# Sheet1.net
KiCad netlist of a schematic drawn in Altium Designer
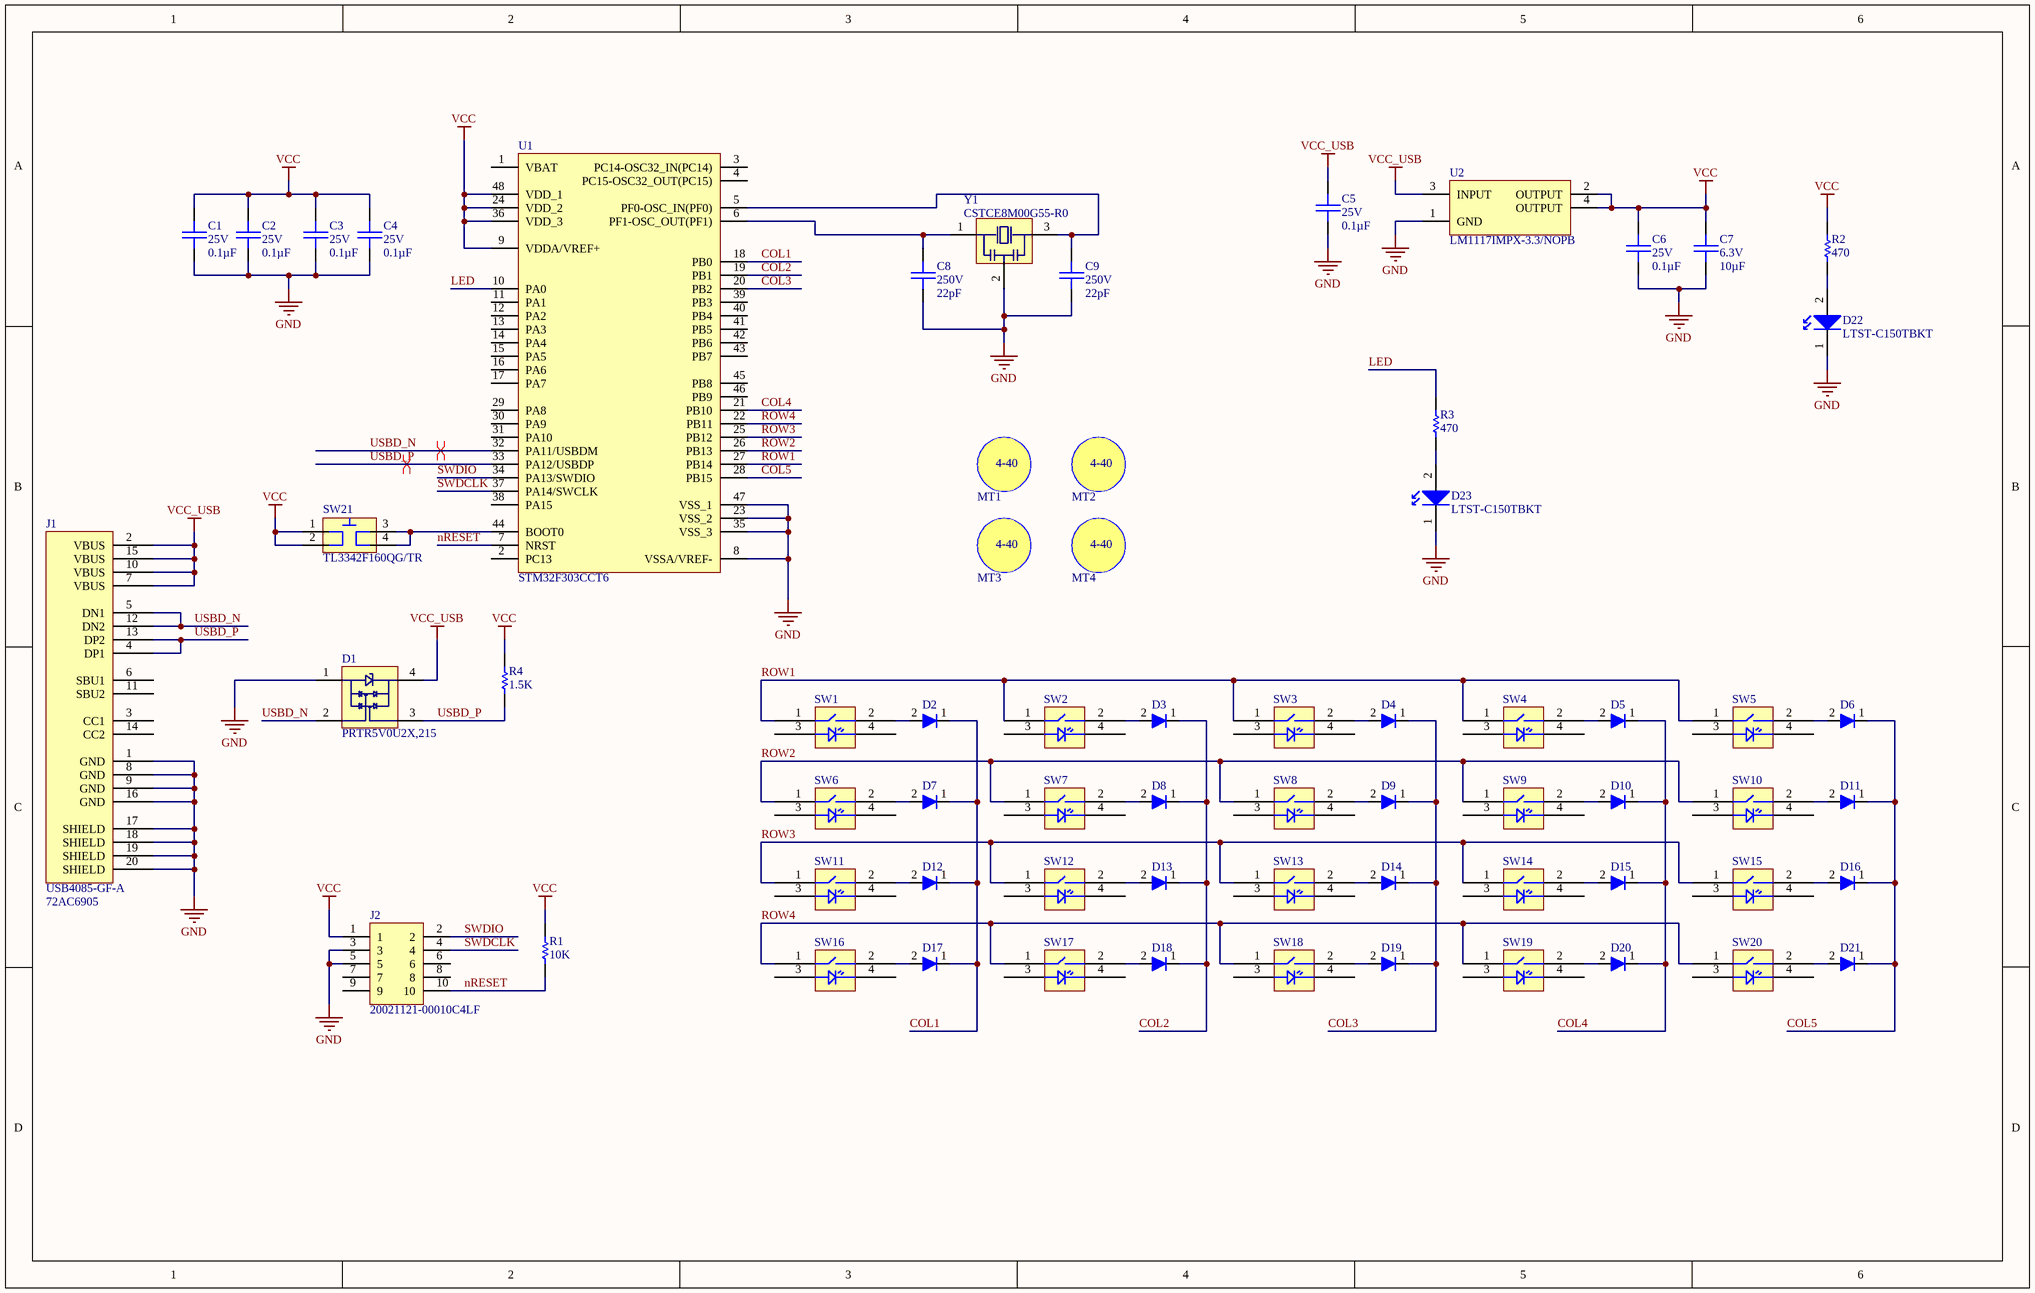
[diagram p0: Sheet1.SchDoc]

(export (version "E")
  (design (tool "Eeschema 10.0.6"))
  (components
    (comp (ref "C1")
      (value "0.1µF")
      (footprint "CAPC_0603(1.6X0.8)_N")
      (description "Generic Capacitor")
      (fields
        (field (name "TOLERANCE") "±10%")
        (field (name "VOLTAGE") "25V")
        (field (name "MANUFACTURER") "Generic")
      )
      (libsource (lib "Safari") (part "CAPC"))
    )
    (comp (ref "C2")
      (value "0.1µF")
      (footprint "CAPC_0603(1.6X0.8)_N")
      (description "Generic Capacitor")
      (fields
        (field (name "TOLERANCE") "±10%")
        (field (name "VOLTAGE") "25V")
        (field (name "MANUFACTURER") "Generic")
      )
      (libsource (lib "Safari") (part "CAPC"))
    )
    (comp (ref "C3")
      (value "0.1µF")
      (footprint "CAPC_0603(1.6X0.8)_N")
      (description "Generic Capacitor")
      (fields
        (field (name "TOLERANCE") "±10%")
        (field (name "VOLTAGE") "25V")
        (field (name "MANUFACTURER") "Generic")
      )
      (libsource (lib "Safari") (part "CAPC"))
    )
    (comp (ref "C4")
      (value "0.1µF")
      (footprint "CAPC_0603(1.6X0.8)_N")
      (description "Generic Capacitor")
      (fields
        (field (name "TOLERANCE") "±10%")
        (field (name "VOLTAGE") "25V")
        (field (name "MANUFACTURER") "Generic")
      )
      (libsource (lib "Safari") (part "CAPC"))
    )
    (comp (ref "C5")
      (value "0.1µF")
      (footprint "CAPC_0603(1.6X0.8)_N")
      (description "Generic Capacitor")
      (fields
        (field (name "TOLERANCE") "±10%")
        (field (name "VOLTAGE") "25V")
        (field (name "MANUFACTURER") "Generic")
      )
      (libsource (lib "Safari") (part "CAPC"))
    )
    (comp (ref "C6")
      (value "0.1µF")
      (footprint "CAPC_0603(1.6X0.8)_N")
      (description "Generic Capacitor")
      (fields
        (field (name "TOLERANCE") "±10%")
        (field (name "VOLTAGE") "25V")
        (field (name "MANUFACTURER") "Generic")
      )
      (libsource (lib "Safari") (part "CAPC"))
    )
    (comp (ref "C7")
      (value "10µF")
      (footprint "CAPC_0603(1.6X0.8)_N")
      (description "Generic Capacitor")
      (fields
        (field (name "TOLERANCE") "±20%")
        (field (name "VOLTAGE") "6.3V")
        (field (name "MANUFACTURER") "Generic")
      )
      (libsource (lib "Safari") (part "CAPC"))
    )
    (comp (ref "C8")
      (value "22pF")
      (footprint "CAPC_0603(1.6X0.8)_N")
      (description "Generic Capacitor")
      (fields
        (field (name "TOLERANCE") "±2%")
        (field (name "VOLTAGE") "250V")
        (field (name "MANUFACTURER") "Generic")
      )
      (libsource (lib "Safari") (part "CAPC"))
    )
    (comp (ref "C9")
      (value "22pF")
      (footprint "CAPC_0603(1.6X0.8)_N")
      (description "Generic Capacitor")
      (fields
        (field (name "TOLERANCE") "±2%")
        (field (name "VOLTAGE") "250V")
        (field (name "MANUFACTURER") "Generic")
      )
      (libsource (lib "Safari") (part "CAPC"))
    )
    (comp (ref "D1")
      (value "TVS DIODE 5.5VWM SOT143B")
      (footprint "NXP_SOT143B_N")
      (fields
        (field (name "MANUFACTURER") "NXP Semiconductors")
        (field (name "MANUFACTURER PART NUMBER") "PRTR5V0U2X,215")
        (field (name "SAFARIPARTNUMBER") "15 27314RC")
      )
      (libsource (lib "Safari") (part "PRTR5V0U2X,215"))
    )
    (comp (ref "D2")
      (value "DIODE GEN PURP 100V 300MA SOD123")
      (footprint "1N4148W-7-F_N")
      (fields
        (field (name "MANUFACTURER") "Diodes Incorporated")
        (field (name "MANUFACTURER PART NUMBER") "1N4148W-7-F")
        (field (name "SAFARIPARTNUMBER") "15 15821RC")
      )
      (libsource (lib "Safari") (part "1N4148W-7-F"))
    )
    (comp (ref "D3")
      (value "DIODE GEN PURP 100V 300MA SOD123")
      (footprint "1N4148W-7-F_N")
      (fields
        (field (name "MANUFACTURER") "Diodes Incorporated")
        (field (name "MANUFACTURER PART NUMBER") "1N4148W-7-F")
        (field (name "SAFARIPARTNUMBER") "15 15821RC")
      )
      (libsource (lib "Safari") (part "1N4148W-7-F"))
    )
    (comp (ref "D4")
      (value "DIODE GEN PURP 100V 300MA SOD123")
      (footprint "1N4148W-7-F_N")
      (fields
        (field (name "MANUFACTURER") "Diodes Incorporated")
        (field (name "MANUFACTURER PART NUMBER") "1N4148W-7-F")
        (field (name "SAFARIPARTNUMBER") "15 15821RC")
      )
      (libsource (lib "Safari") (part "1N4148W-7-F"))
    )
    (comp (ref "D5")
      (value "DIODE GEN PURP 100V 300MA SOD123")
      (footprint "1N4148W-7-F_N")
      (fields
        (field (name "MANUFACTURER") "Diodes Incorporated")
        (field (name "MANUFACTURER PART NUMBER") "1N4148W-7-F")
        (field (name "SAFARIPARTNUMBER") "15 15821RC")
      )
      (libsource (lib "Safari") (part "1N4148W-7-F"))
    )
    (comp (ref "D6")
      (value "DIODE GEN PURP 100V 300MA SOD123")
      (footprint "1N4148W-7-F_N")
      (fields
        (field (name "MANUFACTURER") "Diodes Incorporated")
        (field (name "MANUFACTURER PART NUMBER") "1N4148W-7-F")
        (field (name "SAFARIPARTNUMBER") "15 15821RC")
      )
      (libsource (lib "Safari") (part "1N4148W-7-F"))
    )
    (comp (ref "D7")
      (value "DIODE GEN PURP 100V 300MA SOD123")
      (footprint "1N4148W-7-F_N")
      (fields
        (field (name "MANUFACTURER") "Diodes Incorporated")
        (field (name "MANUFACTURER PART NUMBER") "1N4148W-7-F")
        (field (name "SAFARIPARTNUMBER") "15 15821RC")
      )
      (libsource (lib "Safari") (part "1N4148W-7-F"))
    )
    (comp (ref "D8")
      (value "DIODE GEN PURP 100V 300MA SOD123")
      (footprint "1N4148W-7-F_N")
      (fields
        (field (name "MANUFACTURER") "Diodes Incorporated")
        (field (name "MANUFACTURER PART NUMBER") "1N4148W-7-F")
        (field (name "SAFARIPARTNUMBER") "15 15821RC")
      )
      (libsource (lib "Safari") (part "1N4148W-7-F"))
    )
    (comp (ref "D9")
      (value "DIODE GEN PURP 100V 300MA SOD123")
      (footprint "1N4148W-7-F_N")
      (fields
        (field (name "MANUFACTURER") "Diodes Incorporated")
        (field (name "MANUFACTURER PART NUMBER") "1N4148W-7-F")
        (field (name "SAFARIPARTNUMBER") "15 15821RC")
      )
      (libsource (lib "Safari") (part "1N4148W-7-F"))
    )
    (comp (ref "D10")
      (value "DIODE GEN PURP 100V 300MA SOD123")
      (footprint "1N4148W-7-F_N")
      (fields
        (field (name "MANUFACTURER") "Diodes Incorporated")
        (field (name "MANUFACTURER PART NUMBER") "1N4148W-7-F")
        (field (name "SAFARIPARTNUMBER") "15 15821RC")
      )
      (libsource (lib "Safari") (part "1N4148W-7-F"))
    )
    (comp (ref "D11")
      (value "DIODE GEN PURP 100V 300MA SOD123")
      (footprint "1N4148W-7-F_N")
      (fields
        (field (name "MANUFACTURER") "Diodes Incorporated")
        (field (name "MANUFACTURER PART NUMBER") "1N4148W-7-F")
        (field (name "SAFARIPARTNUMBER") "15 15821RC")
      )
      (libsource (lib "Safari") (part "1N4148W-7-F"))
    )
    (comp (ref "D12")
      (value "DIODE GEN PURP 100V 300MA SOD123")
      (footprint "1N4148W-7-F_N")
      (fields
        (field (name "MANUFACTURER") "Diodes Incorporated")
        (field (name "MANUFACTURER PART NUMBER") "1N4148W-7-F")
        (field (name "SAFARIPARTNUMBER") "15 15821RC")
      )
      (libsource (lib "Safari") (part "1N4148W-7-F"))
    )
    (comp (ref "D13")
      (value "DIODE GEN PURP 100V 300MA SOD123")
      (footprint "1N4148W-7-F_N")
      (fields
        (field (name "MANUFACTURER") "Diodes Incorporated")
        (field (name "MANUFACTURER PART NUMBER") "1N4148W-7-F")
        (field (name "SAFARIPARTNUMBER") "15 15821RC")
      )
      (libsource (lib "Safari") (part "1N4148W-7-F"))
    )
    (comp (ref "D14")
      (value "DIODE GEN PURP 100V 300MA SOD123")
      (footprint "1N4148W-7-F_N")
      (fields
        (field (name "MANUFACTURER") "Diodes Incorporated")
        (field (name "MANUFACTURER PART NUMBER") "1N4148W-7-F")
        (field (name "SAFARIPARTNUMBER") "15 15821RC")
      )
      (libsource (lib "Safari") (part "1N4148W-7-F"))
    )
    (comp (ref "D15")
      (value "DIODE GEN PURP 100V 300MA SOD123")
      (footprint "1N4148W-7-F_N")
      (fields
        (field (name "MANUFACTURER") "Diodes Incorporated")
        (field (name "MANUFACTURER PART NUMBER") "1N4148W-7-F")
        (field (name "SAFARIPARTNUMBER") "15 15821RC")
      )
      (libsource (lib "Safari") (part "1N4148W-7-F"))
    )
    (comp (ref "D16")
      (value "DIODE GEN PURP 100V 300MA SOD123")
      (footprint "1N4148W-7-F_N")
      (fields
        (field (name "MANUFACTURER") "Diodes Incorporated")
        (field (name "MANUFACTURER PART NUMBER") "1N4148W-7-F")
        (field (name "SAFARIPARTNUMBER") "15 15821RC")
      )
      (libsource (lib "Safari") (part "1N4148W-7-F"))
    )
    (comp (ref "D17")
      (value "DIODE GEN PURP 100V 300MA SOD123")
      (footprint "1N4148W-7-F_N")
      (fields
        (field (name "MANUFACTURER") "Diodes Incorporated")
        (field (name "MANUFACTURER PART NUMBER") "1N4148W-7-F")
        (field (name "SAFARIPARTNUMBER") "15 15821RC")
      )
      (libsource (lib "Safari") (part "1N4148W-7-F"))
    )
    (comp (ref "D18")
      (value "DIODE GEN PURP 100V 300MA SOD123")
      (footprint "1N4148W-7-F_N")
      (fields
        (field (name "MANUFACTURER") "Diodes Incorporated")
        (field (name "MANUFACTURER PART NUMBER") "1N4148W-7-F")
        (field (name "SAFARIPARTNUMBER") "15 15821RC")
      )
      (libsource (lib "Safari") (part "1N4148W-7-F"))
    )
    (comp (ref "D19")
      (value "DIODE GEN PURP 100V 300MA SOD123")
      (footprint "1N4148W-7-F_N")
      (fields
        (field (name "MANUFACTURER") "Diodes Incorporated")
        (field (name "MANUFACTURER PART NUMBER") "1N4148W-7-F")
        (field (name "SAFARIPARTNUMBER") "15 15821RC")
      )
      (libsource (lib "Safari") (part "1N4148W-7-F"))
    )
    (comp (ref "D20")
      (value "DIODE GEN PURP 100V 300MA SOD123")
      (footprint "1N4148W-7-F_N")
      (fields
        (field (name "MANUFACTURER") "Diodes Incorporated")
        (field (name "MANUFACTURER PART NUMBER") "1N4148W-7-F")
        (field (name "SAFARIPARTNUMBER") "15 15821RC")
      )
      (libsource (lib "Safari") (part "1N4148W-7-F"))
    )
    (comp (ref "D21")
      (value "DIODE GEN PURP 100V 300MA SOD123")
      (footprint "1N4148W-7-F_N")
      (fields
        (field (name "MANUFACTURER") "Diodes Incorporated")
        (field (name "MANUFACTURER PART NUMBER") "1N4148W-7-F")
        (field (name "SAFARIPARTNUMBER") "15 15821RC")
      )
      (libsource (lib "Safari") (part "1N4148W-7-F"))
    )
    (comp (ref "D22")
      (value "LED 468NM BLUE CLEAR 1206 SMD")
      (footprint "LTST-C150TBKT_N")
      (fields
        (field (name "MANUFACTURER") "Lite-On Inc")
        (field (name "MANUFACTURER PART NUMBER") "LTST-C150TBKT")
        (field (name "SAFARIPARTNUMBER") "15 25012RC")
      )
      (libsource (lib "Safari") (part "LTST-C150TBKT"))
    )
    (comp (ref "D23")
      (value "LED 468NM BLUE CLEAR 1206 SMD")
      (footprint "LTST-C150TBKT_N")
      (fields
        (field (name "MANUFACTURER") "Lite-On Inc")
        (field (name "MANUFACTURER PART NUMBER") "LTST-C150TBKT")
        (field (name "SAFARIPARTNUMBER") "15 25012RC")
      )
      (libsource (lib "Safari") (part "LTST-C150TBKT"))
    )
    (comp (ref "J1")
      (value "USB4085-GF-A")
      (footprint "GCT_USB4085-GF-A_MN")
      (description "USB4085 Series 20 V PCB Top Mount USB 2.0 Type C Receptacle")
      (fields (field (name "SUPPLIER PART NUMBER 1") "72AC6905"))
      (libsource (lib "USB4085-GF-A") (part "USB4085-GF-A"))
    )
    (comp (ref "J2")
      (value "CONN HEADER 10POS DL UNSHRD SMD")
      (footprint "20021121-00010C4LF")
      (fields
        (field (name "MANUFACTURER") "FCI")
        (field (name "MANUFACTURER PART NUMBER") "20021121-00010C4LF")
      )
      (libsource (lib "Safari") (part "20021121-00010C4LF"))
    )
    (comp (ref "MT1")
      (value "4-40 Mounting hole NPTH")
      (footprint "440LNPTH")
      (fields (field (name "MANUFACTURER PART NUMBER") "4-40_NPTH"))
      (libsource (lib "Safari") (part "4-40_NPTH"))
    )
    (comp (ref "MT2")
      (value "4-40 Mounting hole NPTH")
      (footprint "440LNPTH")
      (fields (field (name "MANUFACTURER PART NUMBER") "4-40_NPTH"))
      (libsource (lib "Safari") (part "4-40_NPTH"))
    )
    (comp (ref "MT3")
      (value "4-40 Mounting hole NPTH")
      (footprint "440LNPTH")
      (fields (field (name "MANUFACTURER PART NUMBER") "4-40_NPTH"))
      (libsource (lib "Safari") (part "4-40_NPTH"))
    )
    (comp (ref "MT4")
      (value "4-40 Mounting hole NPTH")
      (footprint "440LNPTH")
      (fields (field (name "MANUFACTURER PART NUMBER") "4-40_NPTH"))
      (libsource (lib "Safari") (part "4-40_NPTH"))
    )
    (comp (ref "R1")
      (value "10K")
      (footprint "RESC_0603(1.6X0.8)_N")
      (description "Generic Resistor")
      (fields (field (name "TOLERANCE") "5%") (field (name "POWER") "0.1W"))
      (libsource (lib "Safari") (part "RES"))
    )
    (comp (ref "R2")
      (value "470")
      (footprint "RESC_0603(1.6X0.8)_N")
      (description "Generic Resistor")
      (fields (field (name "TOLERANCE") "5%") (field (name "POWER") "0.1W"))
      (libsource (lib "Safari") (part "RES"))
    )
    (comp (ref "R3")
      (value "470")
      (footprint "RESC_0603(1.6X0.8)_N")
      (description "Generic Resistor")
      (fields (field (name "TOLERANCE") "5%") (field (name "POWER") "0.1W"))
      (libsource (lib "Safari") (part "RES"))
    )
    (comp (ref "R4")
      (value "1.5K")
      (footprint "RESC_0603(1.6X0.8)_N")
      (description "Generic Resistor")
      (fields (field (name "TOLERANCE") "5%") (field (name "POWER") "0.1W"))
      (libsource (lib "Safari") (part "RES"))
    )
    (comp (ref "SW1")
      (value "MX1A-E1NW")
      (footprint "CHRY_MXXX-XXXW_MA")
      (description "SWITCH PUSH SPST-NO 0.01A 12V")
      (libsource (lib "MX1A-E1NW") (part "MX1A-E1NW"))
    )
    (comp (ref "SW2")
      (value "MX1A-E1NW")
      (footprint "CHRY_MXXX-XXXW_MA")
      (description "SWITCH PUSH SPST-NO 0.01A 12V")
      (libsource (lib "MX1A-E1NW") (part "MX1A-E1NW"))
    )
    (comp (ref "SW3")
      (value "MX1A-E1NW")
      (footprint "CHRY_MXXX-XXXW_MA")
      (description "SWITCH PUSH SPST-NO 0.01A 12V")
      (libsource (lib "MX1A-E1NW") (part "MX1A-E1NW"))
    )
    (comp (ref "SW4")
      (value "MX1A-E1NW")
      (footprint "CHRY_MXXX-XXXW_MA")
      (description "SWITCH PUSH SPST-NO 0.01A 12V")
      (libsource (lib "MX1A-E1NW") (part "MX1A-E1NW"))
    )
    (comp (ref "SW5")
      (value "MX1A-E1NW")
      (footprint "CHRY_MXXX-XXXW_MA")
      (description "SWITCH PUSH SPST-NO 0.01A 12V")
      (libsource (lib "MX1A-E1NW") (part "MX1A-E1NW"))
    )
    (comp (ref "SW6")
      (value "MX1A-E1NW")
      (footprint "CHRY_MXXX-XXXW_MA")
      (description "SWITCH PUSH SPST-NO 0.01A 12V")
      (libsource (lib "MX1A-E1NW") (part "MX1A-E1NW"))
    )
    (comp (ref "SW7")
      (value "MX1A-E1NW")
      (footprint "CHRY_MXXX-XXXW_MA")
      (description "SWITCH PUSH SPST-NO 0.01A 12V")
      (libsource (lib "MX1A-E1NW") (part "MX1A-E1NW"))
    )
    (comp (ref "SW8")
      (value "MX1A-E1NW")
      (footprint "CHRY_MXXX-XXXW_MA")
      (description "SWITCH PUSH SPST-NO 0.01A 12V")
      (libsource (lib "MX1A-E1NW") (part "MX1A-E1NW"))
    )
    (comp (ref "SW9")
      (value "MX1A-E1NW")
      (footprint "CHRY_MXXX-XXXW_MA")
      (description "SWITCH PUSH SPST-NO 0.01A 12V")
      (libsource (lib "MX1A-E1NW") (part "MX1A-E1NW"))
    )
    (comp (ref "SW10")
      (value "MX1A-E1NW")
      (footprint "CHRY_MXXX-XXXW_MA")
      (description "SWITCH PUSH SPST-NO 0.01A 12V")
      (libsource (lib "MX1A-E1NW") (part "MX1A-E1NW"))
    )
    (comp (ref "SW11")
      (value "MX1A-E1NW")
      (footprint "CHRY_MXXX-XXXW_MA")
      (description "SWITCH PUSH SPST-NO 0.01A 12V")
      (libsource (lib "MX1A-E1NW") (part "MX1A-E1NW"))
    )
    (comp (ref "SW12")
      (value "MX1A-E1NW")
      (footprint "CHRY_MXXX-XXXW_MA")
      (description "SWITCH PUSH SPST-NO 0.01A 12V")
      (libsource (lib "MX1A-E1NW") (part "MX1A-E1NW"))
    )
    (comp (ref "SW13")
      (value "MX1A-E1NW")
      (footprint "CHRY_MXXX-XXXW_MA")
      (description "SWITCH PUSH SPST-NO 0.01A 12V")
      (libsource (lib "MX1A-E1NW") (part "MX1A-E1NW"))
    )
    (comp (ref "SW14")
      (value "MX1A-E1NW")
      (footprint "CHRY_MXXX-XXXW_MA")
      (description "SWITCH PUSH SPST-NO 0.01A 12V")
      (libsource (lib "MX1A-E1NW") (part "MX1A-E1NW"))
    )
    (comp (ref "SW15")
      (value "MX1A-E1NW")
      (footprint "CHRY_MXXX-XXXW_MA")
      (description "SWITCH PUSH SPST-NO 0.01A 12V")
      (libsource (lib "MX1A-E1NW") (part "MX1A-E1NW"))
    )
    (comp (ref "SW16")
      (value "MX1A-E1NW")
      (footprint "CHRY_MXXX-XXXW_MA")
      (description "SWITCH PUSH SPST-NO 0.01A 12V")
      (libsource (lib "MX1A-E1NW") (part "MX1A-E1NW"))
    )
    (comp (ref "SW17")
      (value "MX1A-E1NW")
      (footprint "CHRY_MXXX-XXXW_MA")
      (description "SWITCH PUSH SPST-NO 0.01A 12V")
      (libsource (lib "MX1A-E1NW") (part "MX1A-E1NW"))
    )
    (comp (ref "SW18")
      (value "MX1A-E1NW")
      (footprint "CHRY_MXXX-XXXW_MA")
      (description "SWITCH PUSH SPST-NO 0.01A 12V")
      (libsource (lib "MX1A-E1NW") (part "MX1A-E1NW"))
    )
    (comp (ref "SW19")
      (value "MX1A-E1NW")
      (footprint "CHRY_MXXX-XXXW_MA")
      (description "SWITCH PUSH SPST-NO 0.01A 12V")
      (libsource (lib "MX1A-E1NW") (part "MX1A-E1NW"))
    )
    (comp (ref "SW20")
      (value "MX1A-E1NW")
      (footprint "CHRY_MXXX-XXXW_MA")
      (description "SWITCH PUSH SPST-NO 0.01A 12V")
      (libsource (lib "MX1A-E1NW") (part "MX1A-E1NW"))
    )
    (comp (ref "SW21")
      (value "SWITCH TACTILE SPST-NO 0.05A 12V")
      (footprint "TL3342F160QG-TR")
      (fields
        (field (name "MANUFACTURER") "E-Switch")
        (field (name "MANUFACTURER PART NUMBER") "TL3342F160QG/TR")
      )
      (libsource (lib "Safari") (part "TL3342F160QG-TR"))
    )
    (comp (ref "U1")
      (value "32BIT, CORTEX-M4, 72MHZ, LQFP-48")
      (footprint "ST_LQFP-48-7x7x1.4_MN")
      (fields
        (field (name "MANUFACTURER PART NUMBER 1") "STM32F303CCT6")
        (field (name "MANUFACTURER PART NUMBER") "STM32F303CCT6")
        (field (name "MANUFACTURER") "ST Micro")
      )
      (libsource (lib "Safari") (part "STM32F303CCT6"))
    )
    (comp (ref "U2")
      (value "IC REG LDO 3.3V 0.8A SOT223")
      (footprint "TI_DCY-R-PDSO-G4_N")
      (fields
        (field (name "MANUFACTURER") "Texas Instruments")
        (field (name "MANUFACTURER PART NUMBER") "LM1117IMPX-3.3/NOPB")
        (field (name "SAFARIPARTNUMBER") "15 24656RC")
      )
      (libsource (lib "Safari") (part "LM1117IMPX-3.3-NOPB"))
    )
    (comp (ref "Y1")
      (value "CER RESONATOR 8.00MHZ SMD")
      (footprint "CSTCE8M00G55-R0")
      (fields
        (field (name "MANUFACTURER") "Murata Electronics North America")
        (field (name "MANUFACTURER PART NUMBER") "CSTCE8M00G55-R0")
      )
      (libsource (lib "Safari") (part "CSTCE8M00G55-R0"))
    )
  )
  (nets
    (net (code "1") (name "/COL1") (class "Default")
      (node (ref "D12") (pin "1") (pinfunction "K_1") (pintype "passive"))
      (node (ref "D17") (pin "1") (pinfunction "K_1") (pintype "passive"))
      (node (ref "D2") (pin "1") (pinfunction "K_1") (pintype "passive"))
      (node (ref "D7") (pin "1") (pinfunction "K_1") (pintype "passive"))
      (node (ref "U1") (pin "18") (pinfunction "PB0_18") (pintype "passive"))
    )
    (net (code "2") (name "/COL2") (class "Default")
      (node (ref "D13") (pin "1") (pinfunction "K_1") (pintype "passive"))
      (node (ref "D18") (pin "1") (pinfunction "K_1") (pintype "passive"))
      (node (ref "D3") (pin "1") (pinfunction "K_1") (pintype "passive"))
      (node (ref "D8") (pin "1") (pinfunction "K_1") (pintype "passive"))
      (node (ref "U1") (pin "19") (pinfunction "PB1_19") (pintype "passive"))
    )
    (net (code "3") (name "/COL3") (class "Default")
      (node (ref "D14") (pin "1") (pinfunction "K_1") (pintype "passive"))
      (node (ref "D19") (pin "1") (pinfunction "K_1") (pintype "passive"))
      (node (ref "D4") (pin "1") (pinfunction "K_1") (pintype "passive"))
      (node (ref "D9") (pin "1") (pinfunction "K_1") (pintype "passive"))
      (node (ref "U1") (pin "20") (pinfunction "PB2_20") (pintype "passive"))
    )
    (net (code "4") (name "/COL4") (class "Default")
      (node (ref "D10") (pin "1") (pinfunction "K_1") (pintype "passive"))
      (node (ref "D15") (pin "1") (pinfunction "K_1") (pintype "passive"))
      (node (ref "D20") (pin "1") (pinfunction "K_1") (pintype "passive"))
      (node (ref "D5") (pin "1") (pinfunction "K_1") (pintype "passive"))
      (node (ref "U1") (pin "21") (pinfunction "PB10_21") (pintype "passive"))
    )
    (net (code "5") (name "/COL5") (class "Default")
      (node (ref "D11") (pin "1") (pinfunction "K_1") (pintype "passive"))
      (node (ref "D16") (pin "1") (pinfunction "K_1") (pintype "passive"))
      (node (ref "D21") (pin "1") (pinfunction "K_1") (pintype "passive"))
      (node (ref "D6") (pin "1") (pinfunction "K_1") (pintype "passive"))
      (node (ref "U1") (pin "28") (pinfunction "PB15_28") (pintype "passive"))
    )
    (net (code "6") (name "/LED") (class "Default")
      (node (ref "R3") (pin "2") (pinfunction "2_2") (pintype "passive"))
      (node (ref "U1") (pin "10") (pinfunction "PA0_10") (pintype "passive"))
    )
    (net (code "7") (name "/ROW1") (class "Default")
      (node (ref "SW1") (pin "1") (pinfunction "1_1") (pintype "passive"))
      (node (ref "SW2") (pin "1") (pinfunction "1_1") (pintype "passive"))
      (node (ref "SW3") (pin "1") (pinfunction "1_1") (pintype "passive"))
      (node (ref "SW4") (pin "1") (pinfunction "1_1") (pintype "passive"))
      (node (ref "SW5") (pin "1") (pinfunction "1_1") (pintype "passive"))
      (node (ref "U1") (pin "27") (pinfunction "PB14_27") (pintype "passive"))
    )
    (net (code "8") (name "/ROW2") (class "Default")
      (node (ref "SW10") (pin "1") (pinfunction "1_1") (pintype "passive"))
      (node (ref "SW6") (pin "1") (pinfunction "1_1") (pintype "passive"))
      (node (ref "SW7") (pin "1") (pinfunction "1_1") (pintype "passive"))
      (node (ref "SW8") (pin "1") (pinfunction "1_1") (pintype "passive"))
      (node (ref "SW9") (pin "1") (pinfunction "1_1") (pintype "passive"))
      (node (ref "U1") (pin "26") (pinfunction "PB13_26") (pintype "passive"))
    )
    (net (code "9") (name "/ROW3") (class "Default")
      (node (ref "SW11") (pin "1") (pinfunction "1_1") (pintype "passive"))
      (node (ref "SW12") (pin "1") (pinfunction "1_1") (pintype "passive"))
      (node (ref "SW13") (pin "1") (pinfunction "1_1") (pintype "passive"))
      (node (ref "SW14") (pin "1") (pinfunction "1_1") (pintype "passive"))
      (node (ref "SW15") (pin "1") (pinfunction "1_1") (pintype "passive"))
      (node (ref "U1") (pin "25") (pinfunction "PB12_25") (pintype "passive"))
    )
    (net (code "10") (name "/ROW4") (class "Default")
      (node (ref "SW16") (pin "1") (pinfunction "1_1") (pintype "passive"))
      (node (ref "SW17") (pin "1") (pinfunction "1_1") (pintype "passive"))
      (node (ref "SW18") (pin "1") (pinfunction "1_1") (pintype "passive"))
      (node (ref "SW19") (pin "1") (pinfunction "1_1") (pintype "passive"))
      (node (ref "SW20") (pin "1") (pinfunction "1_1") (pintype "passive"))
      (node (ref "U1") (pin "22") (pinfunction "PB11_22") (pintype "passive"))
    )
    (net (code "11") (name "/SWDCLK") (class "Default")
      (node (ref "J2") (pin "4") (pinfunction "4_4") (pintype "passive"))
      (node (ref "U1") (pin "37") (pinfunction "PA14/SWCLK_37") (pintype "passive"))
    )
    (net (code "12") (name "/SWDIO") (class "Default")
      (node (ref "J2") (pin "2") (pinfunction "2_2") (pintype "passive"))
      (node (ref "U1") (pin "34") (pinfunction "PA13/SWDIO_34") (pintype "passive"))
    )
    (net (code "13") (name "/USBD_N") (class "Default")
      (node (ref "D1") (pin "2") (pinfunction "IO1_2") (pintype "passive"))
      (node (ref "J1") (pin "12") (pinfunction "DN2_12") (pintype "passive"))
      (node (ref "J1") (pin "5") (pinfunction "DN1_5") (pintype "passive"))
      (node (ref "U1") (pin "32") (pinfunction "PA11/USBDM_32") (pintype "passive"))
    )
    (net (code "14") (name "/USBD_P") (class "Default")
      (node (ref "D1") (pin "3") (pinfunction "IO2_3") (pintype "passive"))
      (node (ref "J1") (pin "13") (pinfunction "DP2_13") (pintype "passive"))
      (node (ref "J1") (pin "4") (pinfunction "DP1_4") (pintype "passive"))
      (node (ref "R4") (pin "1") (pinfunction "1_1") (pintype "passive"))
      (node (ref "U1") (pin "33") (pinfunction "PA12/USBDP_33") (pintype "passive"))
    )
    (net (code "15") (name "/nRESET") (class "Default")
      (node (ref "J2") (pin "10") (pinfunction "10_10") (pintype "passive"))
      (node (ref "R1") (pin "1") (pinfunction "1_1") (pintype "passive"))
      (node (ref "U1") (pin "7") (pinfunction "NRST_7") (pintype "passive"))
    )
    (net (code "16") (name "GND") (class "Default")
      (node (ref "C1") (pin "2") (pinfunction "2_2") (pintype "passive"))
      (node (ref "C2") (pin "2") (pinfunction "2_2") (pintype "passive"))
      (node (ref "C3") (pin "2") (pinfunction "2_2") (pintype "passive"))
      (node (ref "C4") (pin "2") (pinfunction "2_2") (pintype "passive"))
      (node (ref "C5") (pin "2") (pinfunction "2_2") (pintype "passive"))
      (node (ref "C6") (pin "2") (pinfunction "2_2") (pintype "passive"))
      (node (ref "C7") (pin "2") (pinfunction "2_2") (pintype "passive"))
      (node (ref "C8") (pin "2") (pinfunction "2_2") (pintype "passive"))
      (node (ref "C9") (pin "2") (pinfunction "2_2") (pintype "passive"))
      (node (ref "D1") (pin "1") (pinfunction "GND_1") (pintype "passive"))
      (node (ref "D22") (pin "1") (pinfunction "K_1") (pintype "passive"))
      (node (ref "D23") (pin "1") (pinfunction "K_1") (pintype "passive"))
      (node (ref "J1") (pin "1") (pinfunction "GND_1") (pintype "passive"))
      (node (ref "J1") (pin "16") (pinfunction "GND_16") (pintype "passive"))
      (node (ref "J1") (pin "17") (pinfunction "SHIELD_17") (pintype "passive"))
      (node (ref "J1") (pin "18") (pinfunction "SHIELD_18") (pintype "passive"))
      (node (ref "J1") (pin "19") (pinfunction "SHIELD_19") (pintype "passive"))
      (node (ref "J1") (pin "20") (pinfunction "SHIELD_20") (pintype "passive"))
      (node (ref "J1") (pin "8") (pinfunction "GND_8") (pintype "passive"))
      (node (ref "J1") (pin "9") (pinfunction "GND_9") (pintype "passive"))
      (node (ref "J2") (pin "3") (pinfunction "3_3") (pintype "passive"))
      (node (ref "J2") (pin "5") (pinfunction "5_5") (pintype "passive"))
      (node (ref "U1") (pin "23") (pinfunction "VSS_2_23") (pintype "passive"))
      (node (ref "U1") (pin "35") (pinfunction "VSS_3_35") (pintype "passive"))
      (node (ref "U1") (pin "47") (pinfunction "VSS_1_47") (pintype "passive"))
      (node (ref "U1") (pin "8") (pinfunction "VSSA/VREF-_8") (pintype "passive"))
      (node (ref "U2") (pin "1") (pinfunction "GND_1") (pintype "passive"))
      (node (ref "Y1") (pin "2") (pinfunction "2_2") (pintype "passive"))
    )
    (net (code "17") (name "Net-(D2-A)") (class "Default")
      (node (ref "D2") (pin "2") (pinfunction "A_2") (pintype "passive"))
      (node (ref "SW1") (pin "2") (pinfunction "2_2") (pintype "passive"))
    )
    (net (code "18") (name "Net-(D3-A)") (class "Default")
      (node (ref "D3") (pin "2") (pinfunction "A_2") (pintype "passive"))
      (node (ref "SW2") (pin "2") (pinfunction "2_2") (pintype "passive"))
    )
    (net (code "19") (name "Net-(D4-A)") (class "Default")
      (node (ref "D4") (pin "2") (pinfunction "A_2") (pintype "passive"))
      (node (ref "SW3") (pin "2") (pinfunction "2_2") (pintype "passive"))
    )
    (net (code "20") (name "Net-(D5-A)") (class "Default")
      (node (ref "D5") (pin "2") (pinfunction "A_2") (pintype "passive"))
      (node (ref "SW4") (pin "2") (pinfunction "2_2") (pintype "passive"))
    )
    (net (code "21") (name "Net-(D6-A)") (class "Default")
      (node (ref "D6") (pin "2") (pinfunction "A_2") (pintype "passive"))
      (node (ref "SW5") (pin "2") (pinfunction "2_2") (pintype "passive"))
    )
    (net (code "22") (name "Net-(D7-A)") (class "Default")
      (node (ref "D7") (pin "2") (pinfunction "A_2") (pintype "passive"))
      (node (ref "SW6") (pin "2") (pinfunction "2_2") (pintype "passive"))
    )
    (net (code "23") (name "Net-(D8-A)") (class "Default")
      (node (ref "D8") (pin "2") (pinfunction "A_2") (pintype "passive"))
      (node (ref "SW7") (pin "2") (pinfunction "2_2") (pintype "passive"))
    )
    (net (code "24") (name "Net-(D9-A)") (class "Default")
      (node (ref "D9") (pin "2") (pinfunction "A_2") (pintype "passive"))
      (node (ref "SW8") (pin "2") (pinfunction "2_2") (pintype "passive"))
    )
    (net (code "25") (name "Net-(D10-A)") (class "Default")
      (node (ref "D10") (pin "2") (pinfunction "A_2") (pintype "passive"))
      (node (ref "SW9") (pin "2") (pinfunction "2_2") (pintype "passive"))
    )
    (net (code "26") (name "Net-(D11-A)") (class "Default")
      (node (ref "D11") (pin "2") (pinfunction "A_2") (pintype "passive"))
      (node (ref "SW10") (pin "2") (pinfunction "2_2") (pintype "passive"))
    )
    (net (code "27") (name "Net-(D12-A)") (class "Default")
      (node (ref "D12") (pin "2") (pinfunction "A_2") (pintype "passive"))
      (node (ref "SW11") (pin "2") (pinfunction "2_2") (pintype "passive"))
    )
    (net (code "28") (name "Net-(D13-A)") (class "Default")
      (node (ref "D13") (pin "2") (pinfunction "A_2") (pintype "passive"))
      (node (ref "SW12") (pin "2") (pinfunction "2_2") (pintype "passive"))
    )
    (net (code "29") (name "Net-(D14-A)") (class "Default")
      (node (ref "D14") (pin "2") (pinfunction "A_2") (pintype "passive"))
      (node (ref "SW13") (pin "2") (pinfunction "2_2") (pintype "passive"))
    )
    (net (code "30") (name "Net-(D15-A)") (class "Default")
      (node (ref "D15") (pin "2") (pinfunction "A_2") (pintype "passive"))
      (node (ref "SW14") (pin "2") (pinfunction "2_2") (pintype "passive"))
    )
    (net (code "31") (name "Net-(D16-A)") (class "Default")
      (node (ref "D16") (pin "2") (pinfunction "A_2") (pintype "passive"))
      (node (ref "SW15") (pin "2") (pinfunction "2_2") (pintype "passive"))
    )
    (net (code "32") (name "Net-(D17-A)") (class "Default")
      (node (ref "D17") (pin "2") (pinfunction "A_2") (pintype "passive"))
      (node (ref "SW16") (pin "2") (pinfunction "2_2") (pintype "passive"))
    )
    (net (code "33") (name "Net-(D18-A)") (class "Default")
      (node (ref "D18") (pin "2") (pinfunction "A_2") (pintype "passive"))
      (node (ref "SW17") (pin "2") (pinfunction "2_2") (pintype "passive"))
    )
    (net (code "34") (name "Net-(D19-A)") (class "Default")
      (node (ref "D19") (pin "2") (pinfunction "A_2") (pintype "passive"))
      (node (ref "SW18") (pin "2") (pinfunction "2_2") (pintype "passive"))
    )
    (net (code "35") (name "Net-(D20-A)") (class "Default")
      (node (ref "D20") (pin "2") (pinfunction "A_2") (pintype "passive"))
      (node (ref "SW19") (pin "2") (pinfunction "2_2") (pintype "passive"))
    )
    (net (code "36") (name "Net-(D21-A)") (class "Default")
      (node (ref "D21") (pin "2") (pinfunction "A_2") (pintype "passive"))
      (node (ref "SW20") (pin "2") (pinfunction "2_2") (pintype "passive"))
    )
    (net (code "37") (name "Net-(D22-A)") (class "Default")
      (node (ref "D22") (pin "2") (pinfunction "A_2") (pintype "passive"))
      (node (ref "R2") (pin "1") (pinfunction "1_1") (pintype "passive"))
    )
    (net (code "38") (name "Net-(D23-A)") (class "Default")
      (node (ref "D23") (pin "2") (pinfunction "A_2") (pintype "passive"))
      (node (ref "R3") (pin "1") (pinfunction "1_1") (pintype "passive"))
    )
    (net (code "39") (name "Net-(U1-BOOT0)") (class "Default")
      (node (ref "SW21") (pin "3") (pinfunction "3_3") (pintype "passive"))
      (node (ref "SW21") (pin "4") (pinfunction "4_4") (pintype "passive"))
      (node (ref "U1") (pin "44") (pinfunction "BOOT0_44") (pintype "passive"))
    )
    (net (code "40") (name "Net-(U1-PF0-OSC_IN(PF0))") (class "Default")
      (node (ref "C9") (pin "1") (pinfunction "1_1") (pintype "passive"))
      (node (ref "U1") (pin "5") (pinfunction "PF0-OSC_IN(PF0)_5") (pintype "passive"))
      (node (ref "Y1") (pin "3") (pinfunction "3_3") (pintype "passive"))
    )
    (net (code "41") (name "Net-(U1-PF1-OSC_OUT(PF1))") (class "Default")
      (node (ref "C8") (pin "1") (pinfunction "1_1") (pintype "passive"))
      (node (ref "U1") (pin "6") (pinfunction "PF1-OSC_OUT(PF1)_6") (pintype "passive"))
      (node (ref "Y1") (pin "1") (pinfunction "1_1") (pintype "passive"))
    )
    (net (code "42") (name "VCC") (class "Default")
      (node (ref "C1") (pin "1") (pinfunction "1_1") (pintype "passive"))
      (node (ref "C2") (pin "1") (pinfunction "1_1") (pintype "passive"))
      (node (ref "C3") (pin "1") (pinfunction "1_1") (pintype "passive"))
      (node (ref "C4") (pin "1") (pinfunction "1_1") (pintype "passive"))
      (node (ref "C6") (pin "1") (pinfunction "1_1") (pintype "passive"))
      (node (ref "C7") (pin "1") (pinfunction "1_1") (pintype "passive"))
      (node (ref "J2") (pin "1") (pinfunction "1_1") (pintype "passive"))
      (node (ref "R1") (pin "2") (pinfunction "2_2") (pintype "passive"))
      (node (ref "R2") (pin "2") (pinfunction "2_2") (pintype "passive"))
      (node (ref "R4") (pin "2") (pinfunction "2_2") (pintype "passive"))
      (node (ref "SW21") (pin "1") (pinfunction "1_1") (pintype "passive"))
      (node (ref "SW21") (pin "2") (pinfunction "2_2") (pintype "passive"))
      (node (ref "U1") (pin "24") (pinfunction "VDD_2_24") (pintype "passive"))
      (node (ref "U1") (pin "36") (pinfunction "VDD_3_36") (pintype "passive"))
      (node (ref "U1") (pin "48") (pinfunction "VDD_1_48") (pintype "passive"))
      (node (ref "U1") (pin "9") (pinfunction "VDDA/VREF+_9") (pintype "passive"))
      (node (ref "U2") (pin "2") (pinfunction "OUTPUT_2") (pintype "passive"))
      (node (ref "U2") (pin "4") (pinfunction "OUTPUT_4") (pintype "passive"))
    )
    (net (code "43") (name "VCC_USB") (class "Default")
      (node (ref "C5") (pin "1") (pinfunction "1_1") (pintype "passive"))
      (node (ref "D1") (pin "4") (pinfunction "VCC_4") (pintype "passive"))
      (node (ref "J1") (pin "10") (pinfunction "VBUS_10") (pintype "passive"))
      (node (ref "J1") (pin "15") (pinfunction "VBUS_15") (pintype "passive"))
      (node (ref "J1") (pin "2") (pinfunction "VBUS_2") (pintype "passive"))
      (node (ref "J1") (pin "7") (pinfunction "VBUS_7") (pintype "passive"))
      (node (ref "U2") (pin "3") (pinfunction "INPUT_3") (pintype "passive"))
    )
    (net (code "44") (name "unconnected-(J1-CC1-Pad3)") (class "Default")
      (node (ref "J1") (pin "3") (pinfunction "CC1_3") (pintype "passive"))
    )
    (net (code "45") (name "unconnected-(J1-CC2-Pad14)") (class "Default")
      (node (ref "J1") (pin "14") (pinfunction "CC2_14") (pintype "passive"))
    )
    (net (code "46") (name "unconnected-(J1-SBU1-Pad6)") (class "Default")
      (node (ref "J1") (pin "6") (pinfunction "SBU1_6") (pintype "passive"))
    )
    (net (code "47") (name "unconnected-(J1-SBU2-Pad11)") (class "Default")
      (node (ref "J1") (pin "11") (pinfunction "SBU2_11") (pintype "passive"))
    )
    (net (code "48") (name "unconnected-(J2-Pad6)") (class "Default")
      (node (ref "J2") (pin "6") (pinfunction "6_6") (pintype "passive"))
    )
    (net (code "49") (name "unconnected-(J2-Pad7)") (class "Default")
      (node (ref "J2") (pin "7") (pinfunction "7_7") (pintype "passive"))
    )
    (net (code "50") (name "unconnected-(J2-Pad8)") (class "Default")
      (node (ref "J2") (pin "8") (pinfunction "8_8") (pintype "passive"))
    )
    (net (code "51") (name "unconnected-(J2-Pad9)") (class "Default")
      (node (ref "J2") (pin "9") (pinfunction "9_9") (pintype "passive"))
    )
    (net (code "52") (name "unconnected-(SW1-Pad3)") (class "Default")
      (node (ref "SW1") (pin "3") (pinfunction "3_3") (pintype "passive"))
    )
    (net (code "53") (name "unconnected-(SW1-Pad4)") (class "Default")
      (node (ref "SW1") (pin "4") (pinfunction "4_4") (pintype "passive"))
    )
    (net (code "54") (name "unconnected-(SW2-Pad3)") (class "Default")
      (node (ref "SW2") (pin "3") (pinfunction "3_3") (pintype "passive"))
    )
    (net (code "55") (name "unconnected-(SW2-Pad4)") (class "Default")
      (node (ref "SW2") (pin "4") (pinfunction "4_4") (pintype "passive"))
    )
    (net (code "56") (name "unconnected-(SW3-Pad3)") (class "Default")
      (node (ref "SW3") (pin "3") (pinfunction "3_3") (pintype "passive"))
    )
    (net (code "57") (name "unconnected-(SW3-Pad4)") (class "Default")
      (node (ref "SW3") (pin "4") (pinfunction "4_4") (pintype "passive"))
    )
    (net (code "58") (name "unconnected-(SW4-Pad3)") (class "Default")
      (node (ref "SW4") (pin "3") (pinfunction "3_3") (pintype "passive"))
    )
    (net (code "59") (name "unconnected-(SW4-Pad4)") (class "Default")
      (node (ref "SW4") (pin "4") (pinfunction "4_4") (pintype "passive"))
    )
    (net (code "60") (name "unconnected-(SW5-Pad3)") (class "Default")
      (node (ref "SW5") (pin "3") (pinfunction "3_3") (pintype "passive"))
    )
    (net (code "61") (name "unconnected-(SW5-Pad4)") (class "Default")
      (node (ref "SW5") (pin "4") (pinfunction "4_4") (pintype "passive"))
    )
    (net (code "62") (name "unconnected-(SW6-Pad3)") (class "Default")
      (node (ref "SW6") (pin "3") (pinfunction "3_3") (pintype "passive"))
    )
    (net (code "63") (name "unconnected-(SW6-Pad4)") (class "Default")
      (node (ref "SW6") (pin "4") (pinfunction "4_4") (pintype "passive"))
    )
    (net (code "64") (name "unconnected-(SW7-Pad3)") (class "Default")
      (node (ref "SW7") (pin "3") (pinfunction "3_3") (pintype "passive"))
    )
    (net (code "65") (name "unconnected-(SW7-Pad4)") (class "Default")
      (node (ref "SW7") (pin "4") (pinfunction "4_4") (pintype "passive"))
    )
    (net (code "66") (name "unconnected-(SW8-Pad3)") (class "Default")
      (node (ref "SW8") (pin "3") (pinfunction "3_3") (pintype "passive"))
    )
    (net (code "67") (name "unconnected-(SW8-Pad4)") (class "Default")
      (node (ref "SW8") (pin "4") (pinfunction "4_4") (pintype "passive"))
    )
    (net (code "68") (name "unconnected-(SW9-Pad3)") (class "Default")
      (node (ref "SW9") (pin "3") (pinfunction "3_3") (pintype "passive"))
    )
    (net (code "69") (name "unconnected-(SW9-Pad4)") (class "Default")
      (node (ref "SW9") (pin "4") (pinfunction "4_4") (pintype "passive"))
    )
    (net (code "70") (name "unconnected-(SW10-Pad3)") (class "Default")
      (node (ref "SW10") (pin "3") (pinfunction "3_3") (pintype "passive"))
    )
    (net (code "71") (name "unconnected-(SW10-Pad4)") (class "Default")
      (node (ref "SW10") (pin "4") (pinfunction "4_4") (pintype "passive"))
    )
    (net (code "72") (name "unconnected-(SW11-Pad3)") (class "Default")
      (node (ref "SW11") (pin "3") (pinfunction "3_3") (pintype "passive"))
    )
    (net (code "73") (name "unconnected-(SW11-Pad4)") (class "Default")
      (node (ref "SW11") (pin "4") (pinfunction "4_4") (pintype "passive"))
    )
    (net (code "74") (name "unconnected-(SW12-Pad3)") (class "Default")
      (node (ref "SW12") (pin "3") (pinfunction "3_3") (pintype "passive"))
    )
    (net (code "75") (name "unconnected-(SW12-Pad4)") (class "Default")
      (node (ref "SW12") (pin "4") (pinfunction "4_4") (pintype "passive"))
    )
    (net (code "76") (name "unconnected-(SW13-Pad3)") (class "Default")
      (node (ref "SW13") (pin "3") (pinfunction "3_3") (pintype "passive"))
    )
    (net (code "77") (name "unconnected-(SW13-Pad4)") (class "Default")
      (node (ref "SW13") (pin "4") (pinfunction "4_4") (pintype "passive"))
    )
    (net (code "78") (name "unconnected-(SW14-Pad3)") (class "Default")
      (node (ref "SW14") (pin "3") (pinfunction "3_3") (pintype "passive"))
    )
    (net (code "79") (name "unconnected-(SW14-Pad4)") (class "Default")
      (node (ref "SW14") (pin "4") (pinfunction "4_4") (pintype "passive"))
    )
    (net (code "80") (name "unconnected-(SW15-Pad3)") (class "Default")
      (node (ref "SW15") (pin "3") (pinfunction "3_3") (pintype "passive"))
    )
    (net (code "81") (name "unconnected-(SW15-Pad4)") (class "Default")
      (node (ref "SW15") (pin "4") (pinfunction "4_4") (pintype "passive"))
    )
    (net (code "82") (name "unconnected-(SW16-Pad3)") (class "Default")
      (node (ref "SW16") (pin "3") (pinfunction "3_3") (pintype "passive"))
    )
    (net (code "83") (name "unconnected-(SW16-Pad4)") (class "Default")
      (node (ref "SW16") (pin "4") (pinfunction "4_4") (pintype "passive"))
    )
    (net (code "84") (name "unconnected-(SW17-Pad3)") (class "Default")
      (node (ref "SW17") (pin "3") (pinfunction "3_3") (pintype "passive"))
    )
    (net (code "85") (name "unconnected-(SW17-Pad4)") (class "Default")
      (node (ref "SW17") (pin "4") (pinfunction "4_4") (pintype "passive"))
    )
    (net (code "86") (name "unconnected-(SW18-Pad3)") (class "Default")
      (node (ref "SW18") (pin "3") (pinfunction "3_3") (pintype "passive"))
    )
    (net (code "87") (name "unconnected-(SW18-Pad4)") (class "Default")
      (node (ref "SW18") (pin "4") (pinfunction "4_4") (pintype "passive"))
    )
    (net (code "88") (name "unconnected-(SW19-Pad3)") (class "Default")
      (node (ref "SW19") (pin "3") (pinfunction "3_3") (pintype "passive"))
    )
    (net (code "89") (name "unconnected-(SW19-Pad4)") (class "Default")
      (node (ref "SW19") (pin "4") (pinfunction "4_4") (pintype "passive"))
    )
    (net (code "90") (name "unconnected-(SW20-Pad3)") (class "Default")
      (node (ref "SW20") (pin "3") (pinfunction "3_3") (pintype "passive"))
    )
    (net (code "91") (name "unconnected-(SW20-Pad4)") (class "Default")
      (node (ref "SW20") (pin "4") (pinfunction "4_4") (pintype "passive"))
    )
    (net (code "92") (name "unconnected-(U1-PA1-Pad11)") (class "Default")
      (node (ref "U1") (pin "11") (pinfunction "PA1_11") (pintype "passive"))
    )
    (net (code "93") (name "unconnected-(U1-PA2-Pad12)") (class "Default")
      (node (ref "U1") (pin "12") (pinfunction "PA2_12") (pintype "passive"))
    )
    (net (code "94") (name "unconnected-(U1-PA3-Pad13)") (class "Default")
      (node (ref "U1") (pin "13") (pinfunction "PA3_13") (pintype "passive"))
    )
    (net (code "95") (name "unconnected-(U1-PA4-Pad14)") (class "Default")
      (node (ref "U1") (pin "14") (pinfunction "PA4_14") (pintype "passive"))
    )
    (net (code "96") (name "unconnected-(U1-PA5-Pad15)") (class "Default")
      (node (ref "U1") (pin "15") (pinfunction "PA5_15") (pintype "passive"))
    )
    (net (code "97") (name "unconnected-(U1-PA6-Pad16)") (class "Default")
      (node (ref "U1") (pin "16") (pinfunction "PA6_16") (pintype "passive"))
    )
    (net (code "98") (name "unconnected-(U1-PA7-Pad17)") (class "Default")
      (node (ref "U1") (pin "17") (pinfunction "PA7_17") (pintype "passive"))
    )
    (net (code "99") (name "unconnected-(U1-PA8-Pad29)") (class "Default")
      (node (ref "U1") (pin "29") (pinfunction "PA8_29") (pintype "passive"))
    )
    (net (code "100") (name "unconnected-(U1-PA9-Pad30)") (class "Default")
      (node (ref "U1") (pin "30") (pinfunction "PA9_30") (pintype "passive"))
    )
    (net (code "101") (name "unconnected-(U1-PA10-Pad31)") (class "Default")
      (node (ref "U1") (pin "31") (pinfunction "PA10_31") (pintype "passive"))
    )
    (net (code "102") (name "unconnected-(U1-PA15-Pad38)") (class "Default")
      (node (ref "U1") (pin "38") (pinfunction "PA15_38") (pintype "passive"))
    )
    (net (code "103") (name "unconnected-(U1-PB3-Pad39)") (class "Default")
      (node (ref "U1") (pin "39") (pinfunction "PB3_39") (pintype "passive"))
    )
    (net (code "104") (name "unconnected-(U1-PB4-Pad40)") (class "Default")
      (node (ref "U1") (pin "40") (pinfunction "PB4_40") (pintype "passive"))
    )
    (net (code "105") (name "unconnected-(U1-PB5-Pad41)") (class "Default")
      (node (ref "U1") (pin "41") (pinfunction "PB5_41") (pintype "passive"))
    )
    (net (code "106") (name "unconnected-(U1-PB6-Pad42)") (class "Default")
      (node (ref "U1") (pin "42") (pinfunction "PB6_42") (pintype "passive"))
    )
    (net (code "107") (name "unconnected-(U1-PB7-Pad43)") (class "Default")
      (node (ref "U1") (pin "43") (pinfunction "PB7_43") (pintype "passive"))
    )
    (net (code "108") (name "unconnected-(U1-PB8-Pad45)") (class "Default")
      (node (ref "U1") (pin "45") (pinfunction "PB8_45") (pintype "passive"))
    )
    (net (code "109") (name "unconnected-(U1-PB9-Pad46)") (class "Default")
      (node (ref "U1") (pin "46") (pinfunction "PB9_46") (pintype "passive"))
    )
    (net (code "110") (name "unconnected-(U1-PC13-Pad2)") (class "Default")
      (node (ref "U1") (pin "2") (pinfunction "PC13_2") (pintype "passive"))
    )
    (net (code "111") (name "unconnected-(U1-PC14-OSC32_IN(PC14)-Pad3)") (class "Default")
      (node (ref "U1") (pin "3") (pinfunction "PC14-OSC32_IN(PC14)_3") (pintype "passive"))
    )
    (net (code "112") (name "unconnected-(U1-PC15-OSC32_OUT(PC15)-Pad4)") (class "Default")
      (node (ref "U1") (pin "4") (pinfunction "PC15-OSC32_OUT(PC15)_4") (pintype "passive"))
    )
    (net (code "113") (name "unconnected-(U1-VBAT-Pad1)") (class "Default")
      (node (ref "U1") (pin "1") (pinfunction "VBAT_1") (pintype "passive"))
    )
  )
)
